# LPCXpresso55SXX_POWER-USB.net
KiCad netlist of a schematic drawn in Altium Designer
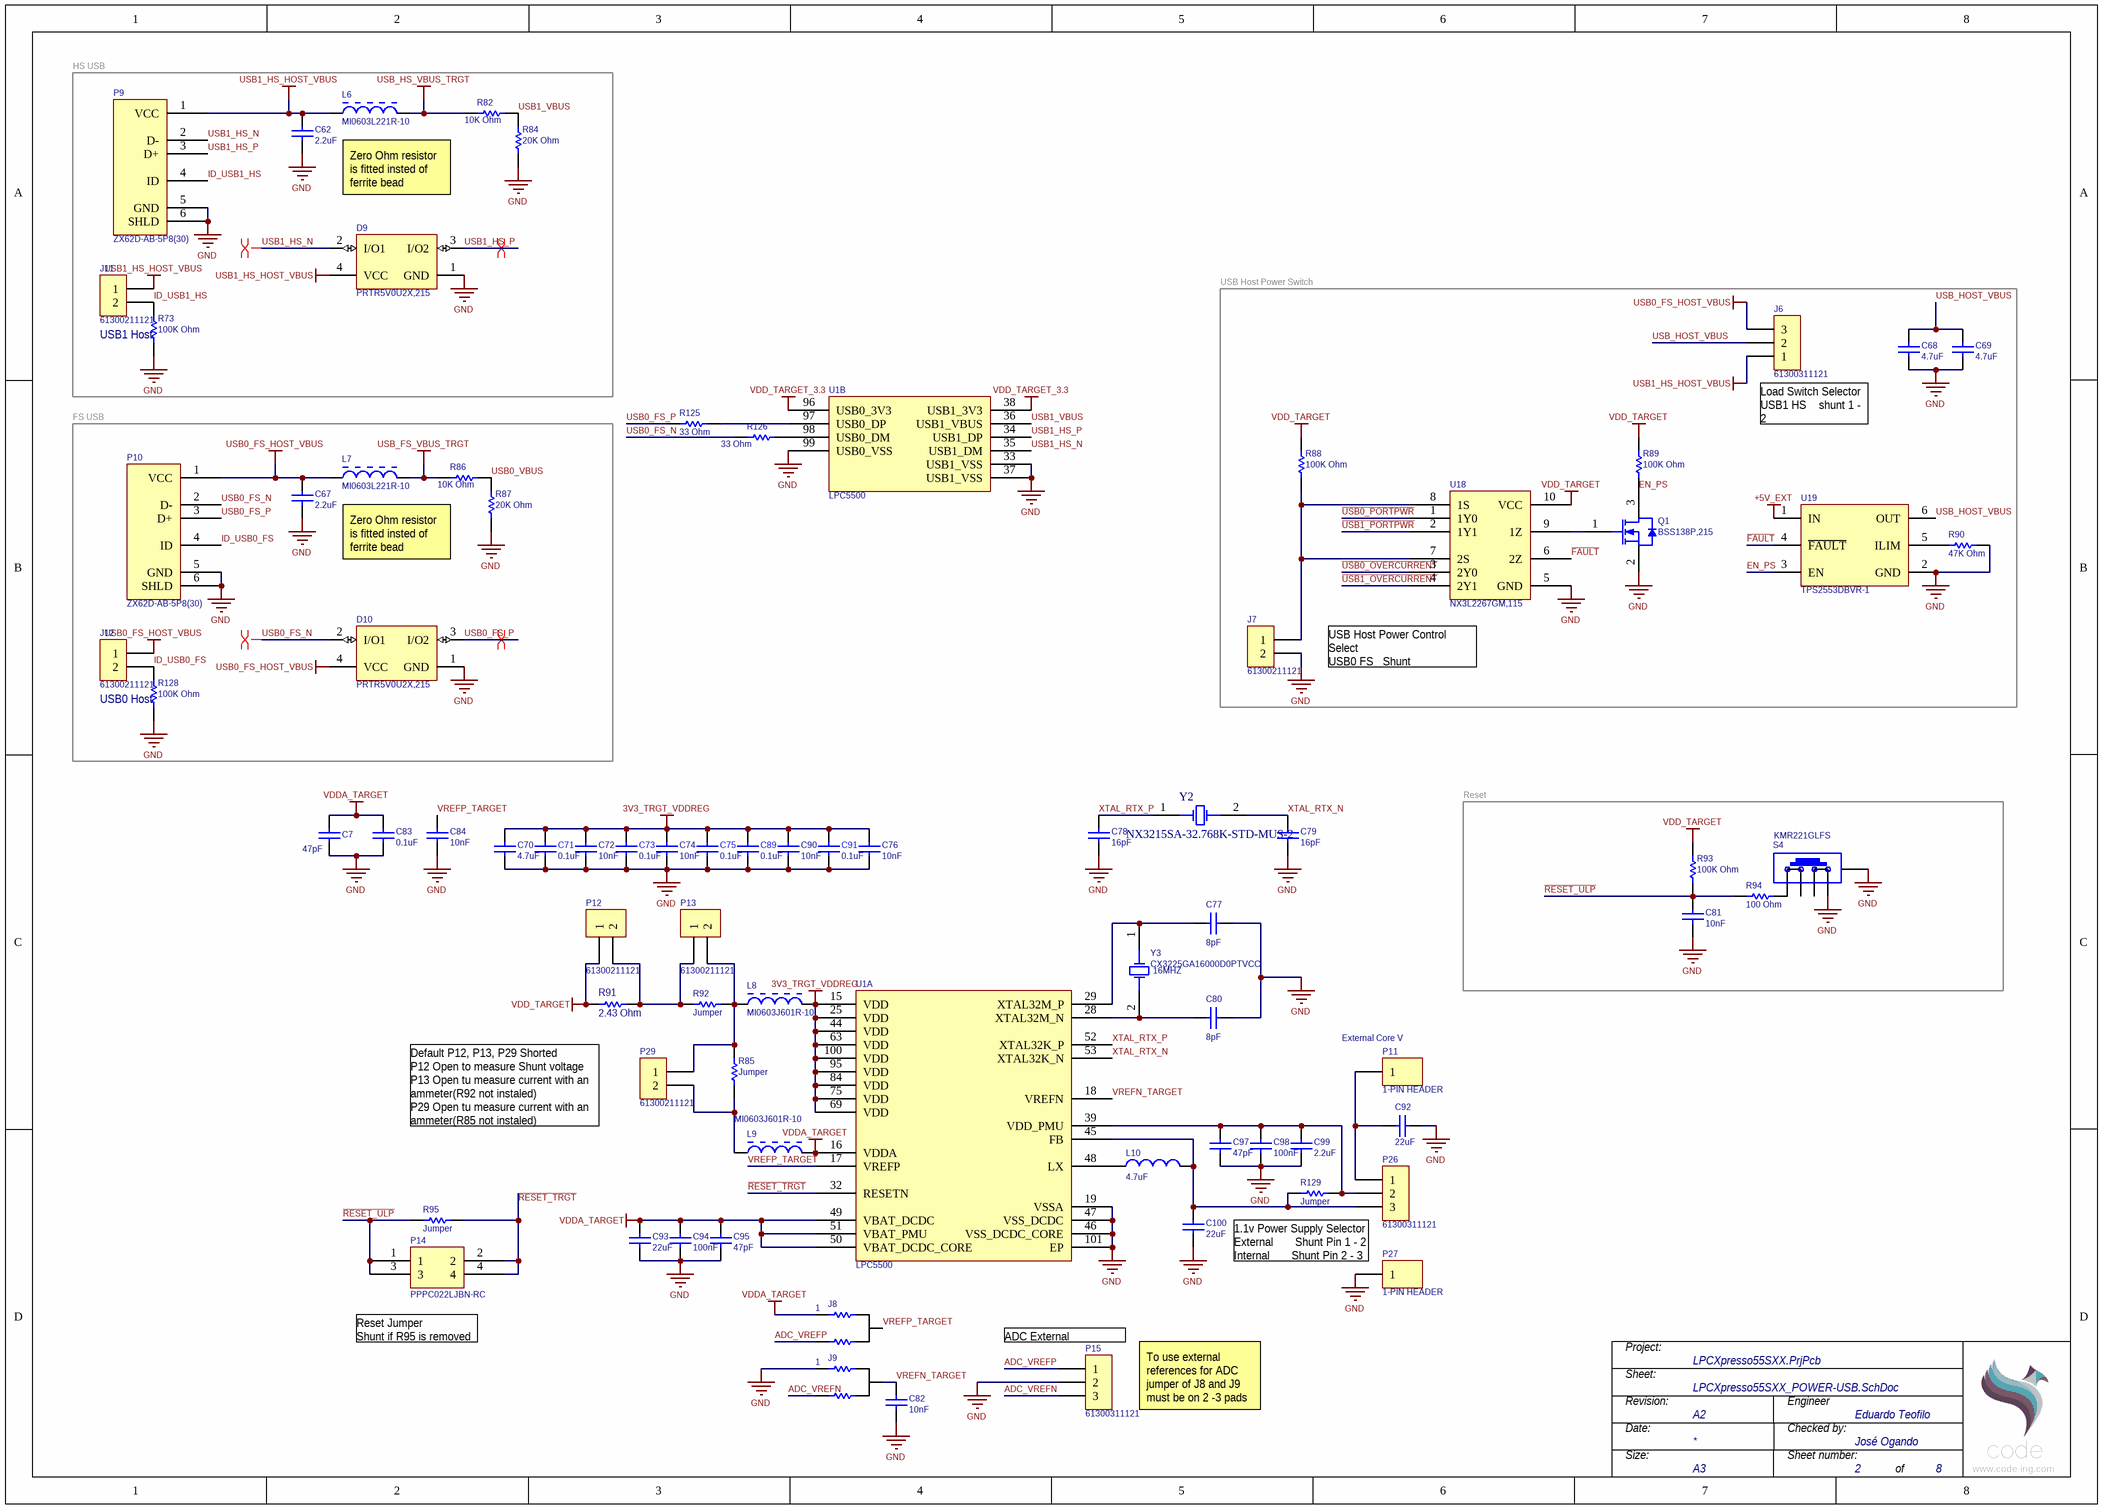
[diagram p0: LPCXpresso55SXX_POWER-USB.SchDoc]

(export (version "E")
  (design (tool "Eeschema 10.0.6"))
  (components
    (comp (ref "C7")
      (value "47pF")
      (footprint "CAPC0402(1005)60_L")
      (description "CAP 47pF 16V ±1% 0402 (1005 Metric) Thickness 0.6mm SMD")
      (fields (field (name "TOLERANCE") "Â±1%") (field (name "Comment") "CAP 47pF 16V 0402(1005)"))
      (libsource (lib "Altium Content Vault") (part "CMP-1034-01078-1"))
    )
    (comp (ref "C62")
      (value "2.2uF")
      (footprint "CAPC0402(1005)60_L")
      (description "CAP 2.2uF 10V ±10% 0402 (1005 Metric) Thickness 0.6mm SMD")
      (fields (field (name "TOLERANCE") "Â±10%") (field (name "Comment") "CAP 2.2uF 10V 0402(1005)"))
      (libsource (lib "Altium Content Vault") (part "CMP-1034-02127-1"))
    )
    (comp (ref "C67")
      (value "2.2uF")
      (footprint "CAPC0402(1005)60_L")
      (description "CAP 2.2uF 10V ±10% 0402 (1005 Metric) Thickness 0.6mm SMD")
      (fields (field (name "TOLERANCE") "Â±10%") (field (name "Comment") "CAP 2.2uF 10V 0402(1005)"))
      (libsource (lib "Altium Content Vault") (part "CMP-1034-02127-1"))
    )
    (comp (ref "C68")
      (value "4.7uF")
      (footprint "CAPC0603(1608)100_L")
      (description "CAP 4.7uF 10V ±10% 0603 (1608 Metric) Thickness 1mm SMD")
      (fields (field (name "TOLERANCE") "Â±10%") (field (name "Comment") "CAP 4.7uF 10V 0603(1608)"))
      (libsource (lib "Altium Content Vault") (part "CMP-1035-02785-1"))
    )
    (comp (ref "C69")
      (value "4.7uF")
      (footprint "CAPC0603(1608)100_L")
      (description "CAP 4.7uF 10V ±10% 0603 (1608 Metric) Thickness 1mm SMD")
      (fields (field (name "TOLERANCE") "Â±10%") (field (name "Comment") "CAP 4.7uF 10V 0603(1608)"))
      (libsource (lib "Altium Content Vault") (part "CMP-1035-02785-1"))
    )
    (comp (ref "C70")
      (value "4.7uF")
      (footprint "CAPC0603(1608)100_L")
      (description "CAP 4.7uF 10V ±10% 0603 (1608 Metric) Thickness 1mm SMD")
      (fields (field (name "TOLERANCE") "Â±10%") (field (name "Comment") "CAP 4.7uF 10V 0603(1608)"))
      (libsource (lib "Altium Content Vault") (part "CMP-1035-02785-1"))
    )
    (comp (ref "C71")
      (value "0.1uF")
      (footprint "CAPC1005")
      (description "Capacitor, Yageo, Ceramic, 0.1uF 10% 16V 0402 (1005) X7R")
      (fields
        (field (name "TOLERANCE") "10 %")
        (field (name "Comment") "CC0402KRX7R7BB104")
        (field (name "PUBLISHER") "Altium")
      )
      (libsource (lib "Altium Content Vault") (part "CMP-0001-00074-1"))
    )
    (comp (ref "C72")
      (value "10nF")
      (footprint "CAPC0402(1005)60_L")
      (description "CAP 10nF 25V ±10% 0402 (1005 Metric) Thickness 0.6mm SMD")
      (fields (field (name "TOLERANCE") "Â±10%") (field (name "Comment") "CAP 10nF 25V 0402(1005)"))
      (libsource (lib "Altium Content Vault") (part "CMP-1034-01880-1"))
    )
    (comp (ref "C73")
      (value "0.1uF")
      (footprint "CAPC1005")
      (description "Capacitor, Yageo, Ceramic, 0.1uF 10% 16V 0402 (1005) X7R")
      (fields
        (field (name "TOLERANCE") "10 %")
        (field (name "Comment") "CC0402KRX7R7BB104")
        (field (name "PUBLISHER") "Altium")
      )
      (libsource (lib "Altium Content Vault") (part "CMP-0001-00074-1"))
    )
    (comp (ref "C74")
      (value "10nF")
      (footprint "CAPC0402(1005)60_L")
      (description "CAP 10nF 25V ±10% 0402 (1005 Metric) Thickness 0.6mm SMD")
      (fields (field (name "TOLERANCE") "Â±10%") (field (name "Comment") "CAP 10nF 25V 0402(1005)"))
      (libsource (lib "Altium Content Vault") (part "CMP-1034-01880-1"))
    )
    (comp (ref "C75")
      (value "0.1uF")
      (footprint "CAPC1005")
      (description "Capacitor, Yageo, Ceramic, 0.1uF 10% 16V 0402 (1005) X7R")
      (fields
        (field (name "TOLERANCE") "10 %")
        (field (name "Comment") "CC0402KRX7R7BB104")
        (field (name "PUBLISHER") "Altium")
      )
      (libsource (lib "Altium Content Vault") (part "CMP-0001-00074-1"))
    )
    (comp (ref "C76")
      (value "10nF")
      (footprint "CAPC0402(1005)60_L")
      (description "CAP 10nF 25V ±10% 0402 (1005 Metric) Thickness 0.6mm SMD")
      (fields (field (name "TOLERANCE") "Â±10%") (field (name "Comment") "CAP 10nF 25V 0402(1005)"))
      (libsource (lib "Altium Content Vault") (part "CMP-1034-01880-1"))
    )
    (comp (ref "C77")
      (value "8pF")
      (footprint "0402_L")
      (description "CAP CER 8PF 25V C0G/NP0 0402")
      (fields
        (field (name "MANUFACTURER PART #") "GRM1555C1E8R0CA01D")
        (field (name "MANUFACTURER") "Murata Electronics North America")
        (field (name "MODIFIED BY") "*")
        (field (name "CREATED BY") "*")
      )
      (libsource (lib "CODE Miscellaneous Devices") (part "Capacitor"))
    )
    (comp (ref "C78")
      (value "16pF")
      (footprint "CAPC0402(1005)60_L")
      (description "CAP 16pF 25V ±0.5pF 0402 (1005 Metric) Thickness 0.6mm SMD")
      (fields (field (name "TOLERANCE") "Â±0.5pF") (field (name "Comment") "CAP 16pF 25V 0402(1005)"))
      (libsource (lib "Altium Content Vault") (part "CMP-1034-00833-1"))
    )
    (comp (ref "C79")
      (value "16pF")
      (footprint "CAPC0402(1005)60_L")
      (description "CAP 16pF 25V ±0.5pF 0402 (1005 Metric) Thickness 0.6mm SMD")
      (fields (field (name "TOLERANCE") "Â±0.5pF") (field (name "Comment") "CAP 16pF 25V 0402(1005)"))
      (libsource (lib "Altium Content Vault") (part "CMP-1034-00833-1"))
    )
    (comp (ref "C80")
      (value "8pF")
      (footprint "0402_L")
      (description "CAP CER 8PF 25V C0G/NP0 0402")
      (fields
        (field (name "MANUFACTURER PART #") "GRM1555C1E8R0CA01D")
        (field (name "MANUFACTURER") "Murata Electronics North America")
        (field (name "MODIFIED BY") "*")
        (field (name "CREATED BY") "*")
      )
      (libsource (lib "CODE Miscellaneous Devices") (part "Capacitor"))
    )
    (comp (ref "C81")
      (value "10nF")
      (footprint "CAPC0402(1005)60_L")
      (description "CAP 10nF 25V ±10% 0402 (1005 Metric) Thickness 0.6mm SMD")
      (fields (field (name "TOLERANCE") "Â±10%") (field (name "Comment") "CAP 10nF 25V 0402(1005)"))
      (libsource (lib "Altium Content Vault") (part "CMP-1034-01880-1"))
    )
    (comp (ref "C82")
      (value "10nF")
      (footprint "CAPC0402(1005)60_L")
      (description "CAP 10nF 25V ±10% 0402 (1005 Metric) Thickness 0.6mm SMD")
      (fields (field (name "TOLERANCE") "Â±10%") (field (name "Comment") "CAP 10nF 25V 0402(1005)"))
      (libsource (lib "Altium Content Vault") (part "CMP-1034-01880-1"))
    )
    (comp (ref "C83")
      (value "0.1uF")
      (footprint "CAPC1005")
      (description "Capacitor, Yageo, Ceramic, 0.1uF 10% 16V 0402 (1005) X7R")
      (fields
        (field (name "TOLERANCE") "10 %")
        (field (name "Comment") "CC0402KRX7R7BB104")
        (field (name "PUBLISHER") "Altium")
      )
      (libsource (lib "Altium Content Vault") (part "CMP-0001-00074-1"))
    )
    (comp (ref "C84")
      (value "10nF")
      (footprint "CAPC0402(1005)60_L")
      (description "CAP 10nF 25V ±10% 0402 (1005 Metric) Thickness 0.6mm SMD")
      (fields (field (name "TOLERANCE") "Â±10%") (field (name "Comment") "CAP 10nF 25V 0402(1005)"))
      (libsource (lib "Altium Content Vault") (part "CMP-1034-01880-1"))
    )
    (comp (ref "C89")
      (value "0.1uF")
      (footprint "CAPC1005")
      (description "Capacitor, Yageo, Ceramic, 0.1uF 10% 16V 0402 (1005) X7R")
      (fields
        (field (name "TOLERANCE") "10 %")
        (field (name "Comment") "CC0402KRX7R7BB104")
        (field (name "PUBLISHER") "Altium")
      )
      (libsource (lib "Altium Content Vault") (part "CMP-0001-00074-1"))
    )
    (comp (ref "C90")
      (value "10nF")
      (footprint "CAPC0402(1005)60_L")
      (description "CAP 10nF 25V ±10% 0402 (1005 Metric) Thickness 0.6mm SMD")
      (fields (field (name "TOLERANCE") "Â±10%") (field (name "Comment") "CAP 10nF 25V 0402(1005)"))
      (libsource (lib "Altium Content Vault") (part "CMP-1034-01880-1"))
    )
    (comp (ref "C91")
      (value "0.1uF")
      (footprint "CAPC1005")
      (description "Capacitor, Yageo, Ceramic, 0.1uF 10% 16V 0402 (1005) X7R")
      (fields
        (field (name "TOLERANCE") "10 %")
        (field (name "Comment") "CC0402KRX7R7BB104")
        (field (name "PUBLISHER") "Altium")
      )
      (libsource (lib "Altium Content Vault") (part "CMP-0001-00074-1"))
    )
    (comp (ref "C92")
      (value "22uF")
      (footprint "CAPC0805(2012)145_L")
      (description "CAP 22uF 16V ±20% 0805 (2012 Metric) Thickness 1.45mm SMD")
      (fields (field (name "TOLERANCE") "Â±20%") (field (name "Comment") "CAP 22uF 16V 0805(2012)"))
      (libsource (lib "Altium Content Vault") (part "CMP-1036-04946-1"))
    )
    (comp (ref "C93")
      (value "22uF")
      (footprint "CAPC0805(2012)145_L")
      (description "CAP 22uF 16V ±20% 0805 (2012 Metric) Thickness 1.45mm SMD")
      (fields (field (name "TOLERANCE") "Â±20%") (field (name "Comment") "CAP 22uF 16V 0805(2012)"))
      (libsource (lib "Altium Content Vault") (part "CMP-1036-04946-1"))
    )
    (comp (ref "C94")
      (value "100nF")
      (footprint "CAPC0603(1608)100_L")
      (description "CAP 100nF 25V ±20% 0603 (1608 Metric) Thickness 1mm SMD")
      (fields (field (name "TOLERANCE") "Â±20%") (field (name "Comment") "CAP 100nF 25V 0603(1608)"))
      (libsource (lib "Altium Content Vault") (part "CMP-1035-02589-1"))
    )
    (comp (ref "C95")
      (value "47pF")
      (footprint "CAPC0603(1608)100_L")
      (description "CAP 47pF 16V ±5pF 0603 (1608 Metric) Thickness 1mm SMD")
      (fields (field (name "TOLERANCE") "±5pF") (field (name "Comment") "CAP 47pF 16V 0603(1608)"))
      (libsource (lib "Altium Content Vault") (part "CMP-1035-01048-1"))
    )
    (comp (ref "C97")
      (value "47pF")
      (footprint "CAPC0603(1608)100_L")
      (description "CAP 47pF 16V ±5pF 0603 (1608 Metric) Thickness 1mm SMD")
      (fields (field (name "TOLERANCE") "±5pF") (field (name "Comment") "CAP 47pF 16V 0603(1608)"))
      (libsource (lib "Altium Content Vault") (part "CMP-1035-01048-1"))
    )
    (comp (ref "C98")
      (value "100nF")
      (footprint "CAPC0603(1608)100_L")
      (description "CAP 100nF 25V ±20% 0603 (1608 Metric) Thickness 1mm SMD")
      (fields (field (name "TOLERANCE") "Â±20%") (field (name "Comment") "CAP 100nF 25V 0603(1608)"))
      (libsource (lib "Altium Content Vault") (part "CMP-1035-02589-1"))
    )
    (comp (ref "C99")
      (value "2.2uF")
      (footprint "CAPC0402(1005)60_L")
      (description "CAP 2.2uF 10V ±10% 0402 (1005 Metric) Thickness 0.6mm SMD")
      (fields (field (name "TOLERANCE") "Â±10%") (field (name "Comment") "CAP 2.2uF 10V 0402(1005)"))
      (libsource (lib "Altium Content Vault") (part "CMP-1034-02127-1"))
    )
    (comp (ref "C100")
      (value "22uF")
      (footprint "CAPC0805(2012)145_L")
      (description "CAP 22uF 16V ±20% 0805 (2012 Metric) Thickness 1.45mm SMD")
      (fields (field (name "TOLERANCE") "Â±20%") (field (name "Comment") "CAP 22uF 16V 0805(2012)"))
      (libsource (lib "Altium Content Vault") (part "CMP-1036-04946-1"))
    )
    (comp (ref "D9")
      (value "PRTR5V0U2X,215")
      (footprint "NXP-SOT143B-4_V")
      (fields (field (name "MANUFACTURER") "NXP Semiconductors"))
      (libsource (lib "Altium Content Vault") (part "NXP-PRTR5V0U2X,215-4"))
    )
    (comp (ref "D10")
      (value "PRTR5V0U2X,215")
      (footprint "NXP-SOT143B-4_V")
      (fields (field (name "MANUFACTURER") "NXP Semiconductors"))
      (libsource (lib "Altium Content Vault") (part "NXP-PRTR5V0U2X,215-4"))
    )
    (comp (ref "J6")
      (value "61300311121")
      (footprint "61300311121")
      (description "HEADER 3POS SNGL T/H 2.54MM")
      (fields
        (field (name "MANUFACTURER") "Wurth Electronics Inc")
        (field (name "MODIFIED BY") "*")
        (field (name "CREATED BY") "gmoreno")
      )
      (libsource (lib "") (part "61300311121_1"))
    )
    (comp (ref "J7")
      (value "61300211121")
      (footprint "61300211121")
      (description "HEADER 2POS SNGL T/H 2.54MM")
      (fields
        (field (name "MANUFACTURER") "Wurth Electronics Inc")
        (field (name "MODIFIED BY") "*")
        (field (name "CREATED BY") "gmoreno")
      )
      (libsource (lib "Rectangular - Headers, Male Pins") (part "61300211121"))
    )
    (comp (ref "J8")
      (value "Resistor - Jumper")
      (footprint "0402_R - JMP")
      (fields (field (name "CREATED BY") "*") (field (name "MODIFIED BY") "*"))
      (libsource (lib "CODE Miscellaneous Devices") (part "Resistor - Jumper"))
    )
    (comp (ref "J9")
      (value "Resistor - Jumper")
      (footprint "0402_R - JMP")
      (fields (field (name "CREATED BY") "*") (field (name "MODIFIED BY") "*"))
      (libsource (lib "CODE Miscellaneous Devices") (part "Resistor - Jumper"))
    )
    (comp (ref "J11")
      (value "61300211121")
      (footprint "61300211121")
      (description "HEADER 2POS SNGL T/H 2.54MM")
      (fields
        (field (name "MANUFACTURER") "Wurth Electronics Inc")
        (field (name "MODIFIED BY") "*")
        (field (name "CREATED BY") "gmoreno")
      )
      (libsource (lib "Rectangular - Headers, Male Pins") (part "61300211121"))
    )
    (comp (ref "J12")
      (value "61300211121")
      (footprint "61300211121")
      (description "HEADER 2POS SNGL T/H 2.54MM")
      (fields
        (field (name "MANUFACTURER") "Wurth Electronics Inc")
        (field (name "MODIFIED BY") "*")
        (field (name "CREATED BY") "gmoreno")
      )
      (libsource (lib "Rectangular - Headers, Male Pins") (part "61300211121"))
    )
    (comp (ref "L6")
      (value "MI0603L221R-10")
      (footprint "LIRD-HZ0603C601R-10-2_V")
      (description "Chip Bead, 100 MHz, 2 A, -40 to 125 degC, 2-Pin SMD (0603), RoHS, Tape and Reel")
      (fields (field (name "MANUFACTURER") "LairdTechnologies"))
      (libsource (lib "Altium Content Vault") (part "IND-FB-2"))
    )
    (comp (ref "L7")
      (value "MI0603L221R-10")
      (footprint "LIRD-HZ0603C601R-10-2_V")
      (description "Chip Bead, 100 MHz, 2 A, -40 to 125 degC, 2-Pin SMD (0603), RoHS, Tape and Reel")
      (fields (field (name "MANUFACTURER") "LairdTechnologies"))
      (libsource (lib "Altium Content Vault") (part "IND-FB-2"))
    )
    (comp (ref "L8")
      (value "MI0603J601R-10")
      (footprint "LIRD-MI0603J601R-10_V")
      (description "Ferrite Bead, 600 Ohm, 1 A, -40 to 125 degC, 2-Pin SMD, RoHS, Tape and Reel")
      (fields (field (name "MANUFACTURER") "Laird"))
      (libsource (lib "Altium Content Vault") (part "IND-FB-2"))
    )
    (comp (ref "L9")
      (value "MI0603J601R-10")
      (footprint "LIRD-MI0603J601R-10_V")
      (description "Ferrite Bead, 600 Ohm, 1 A, -40 to 125 degC, 2-Pin SMD, RoHS, Tape and Reel")
      (fields (field (name "MANUFACTURER") "Laird"))
      (libsource (lib "Altium Content Vault") (part "IND-FB-2"))
    )
    (comp (ref "L10")
      (value "4.7uF")
      (footprint "0805(2012)")
      (description "FIXED IND 4.7UH 400MA 340 MOHM")
      (fields
        (field (name "MANUFACTURER PART #") "MLZ2012M4R7HT000")
        (field (name "MANUFACTURER") "TDK Corporation")
        (field (name "MODIFIED BY") "*")
        (field (name "CREATED BY") "eteofilo")
      )
      (libsource (lib "Fixed") (part "MLZ2012M4R7HT000"))
    )
    (comp (ref "P9")
      (value "ZX62D-AB-5P8(30)")
      (footprint "ZX62D-AB-5P8(30)")
      (description "CONN RCPT USB MICRO AB SMD")
      (fields
        (field (name "MANUFACTURER") "Hirose Electric Co Ltd")
        (field (name "CREATED BY") "eteofilo")
        (field (name "MODIFIED BY") "*")
      )
      (libsource (lib "USB, DVI, HDMI Connectors") (part "ZX62D-AB-5P8(30)"))
    )
    (comp (ref "P10")
      (value "ZX62D-AB-5P8(30)")
      (footprint "ZX62D-AB-5P8(30)")
      (description "CONN RCPT USB MICRO AB SMD")
      (fields
        (field (name "MANUFACTURER") "Hirose Electric Co Ltd")
        (field (name "CREATED BY") "eteofilo")
        (field (name "MODIFIED BY") "*")
      )
      (libsource (lib "USB, DVI, HDMI Connectors") (part "ZX62D-AB-5P8(30)"))
    )
    (comp (ref "P11")
      (value "1-PIN HEADER")
      (footprint "HDR1X1")
      (description "PTH HEADER 40MIL DRILL 70MIL PAD")
      (libsource (lib "CODE Miscellaneous Connectors") (part "1-PIN HEADER"))
    )
    (comp (ref "P12")
      (value "61300211121")
      (footprint "61300211121")
      (description "HEADER 2POS SNGL T/H 2.54MM")
      (fields
        (field (name "MANUFACTURER") "Wurth Electronics Inc")
        (field (name "MODIFIED BY") "*")
        (field (name "CREATED BY") "gmoreno")
      )
      (libsource (lib "") (part "61300211121_1"))
    )
    (comp (ref "P13")
      (value "61300211121")
      (footprint "61300211121")
      (description "HEADER 2POS SNGL T/H 2.54MM")
      (fields
        (field (name "MANUFACTURER") "Wurth Electronics Inc")
        (field (name "MODIFIED BY") "*")
        (field (name "CREATED BY") "gmoreno")
      )
      (libsource (lib "") (part "61300211121_1"))
    )
    (comp (ref "P14")
      (value "PPPC022LJBN-RC")
      (footprint "PPPC022LJBN-RC")
      (description "CONN FEMALE 4POS DL .1\" R/A GOLD")
      (fields
        (field (name "MANUFACTURER") "Sullins Connector Solutions")
        (field (name "CREATED BY") "eteofilo")
        (field (name "MODIFIED BY") "*")
      )
      (libsource (lib "Rectangular - Headers, Receptacles, Female Sockets") (part "PPPC022LJBN-RC"))
    )
    (comp (ref "P15")
      (value "61300311121")
      (footprint "61300311121")
      (description "HEADER 3POS SNGL T/H 2.54MM")
      (fields
        (field (name "MANUFACTURER") "Wurth Electronics Inc")
        (field (name "MODIFIED BY") "*")
        (field (name "CREATED BY") "gmoreno")
      )
      (libsource (lib "Rectangular - Headers, Male Pins") (part "61300311121"))
    )
    (comp (ref "P26")
      (value "61300311121")
      (footprint "61300311121")
      (description "HEADER 3POS SNGL T/H 2.54MM")
      (fields
        (field (name "MANUFACTURER") "Wurth Electronics Inc")
        (field (name "MODIFIED BY") "*")
        (field (name "CREATED BY") "gmoreno")
      )
      (libsource (lib "Rectangular - Headers, Male Pins") (part "61300311121"))
    )
    (comp (ref "P27")
      (value "1-PIN HEADER")
      (footprint "HDR1X1")
      (description "PTH HEADER 40MIL DRILL 70MIL PAD")
      (libsource (lib "CODE Miscellaneous Connectors") (part "1-PIN HEADER"))
    )
    (comp (ref "P29")
      (value "61300211121")
      (footprint "61300211121")
      (description "HEADER 2POS SNGL T/H 2.54MM")
      (fields
        (field (name "MANUFACTURER") "Wurth Electronics Inc")
        (field (name "MODIFIED BY") "*")
        (field (name "CREATED BY") "gmoreno")
      )
      (libsource (lib "Rectangular - Headers, Male Pins") (part "61300211121"))
    )
    (comp (ref "Q1")
      (value "BSS138P,215")
      (footprint "NXP-SOT23_N")
      (description "N-Channel Trench MOSFET, 60 V, 0.36 A, -55 to 150 degC, 3-Pin SOT23, Tape and Reel")
      (fields (field (name "MANUFACTURER") "NXP Semiconductors"))
      (libsource (lib "Altium Content Vault") (part "NXP-NMOS-GSD-3_B"))
    )
    (comp (ref "R73")
      (value "100K Ohm")
      (footprint "RESC1005X40X25LL05T05")
      (description "Chip Resistor, 100 KOhm, +/- 1%, 100 mW, -55 to 155 degC, 0402 (1005 Metric), RoHS, Tape and Reel")
      (fields (field (name "TOLERANCE") "1%") (field (name "MANUFACTURER") "Basic Passives"))
      (libsource (lib "Altium Content Vault") (part "CMP-2002-00608-3"))
    )
    (comp (ref "R82")
      (value "10K Ohm")
      (footprint "RESC0402(1005)_N")
      (description "10K 0.063W 1% 0402 (1005 Metric)  SMD")
      (fields (field (name "TOLERANCE") "1 %") (field (name "POWER") "0.063 W"))
      (libsource (lib "Altium Content Vault") (part "CMP-1011-00623-1"))
    )
    (comp (ref "R84")
      (value "20K Ohm")
      (footprint "RESC0402(1005)_M")
      (description "20K 0.063W 1% 0402 (1005 Metric)  SMD")
      (fields (field (name "POWER") "0.063 W") (field (name "TOLERANCE") "1 %"))
      (libsource (lib "Altium Content Vault") (part "CMP-1011-00655-1"))
    )
    (comp (ref "R85")
      (value "Jumper")
      (footprint "RESC0402(1005)_L")
      (description "Jumper 0402 (1005 Metric)")
      (fields (field (name "TOLERANCE") "None"))
      (libsource (lib "Altium Content Vault") (part "CMP-1011-00001-1"))
    )
    (comp (ref "R86")
      (value "10K Ohm")
      (footprint "RESC0402(1005)_N")
      (description "10K 0.063W 1% 0402 (1005 Metric)  SMD")
      (fields (field (name "TOLERANCE") "1 %") (field (name "POWER") "0.063 W"))
      (libsource (lib "Altium Content Vault") (part "CMP-1011-00623-1"))
    )
    (comp (ref "R87")
      (value "20K Ohm")
      (footprint "RESC0402(1005)_M")
      (description "20K 0.063W 1% 0402 (1005 Metric)  SMD")
      (fields (field (name "POWER") "0.063 W") (field (name "TOLERANCE") "1 %"))
      (libsource (lib "Altium Content Vault") (part "CMP-1011-00655-1"))
    )
    (comp (ref "R88")
      (value "100K Ohm")
      (footprint "RESC1005X40X25LL05T05")
      (description "Chip Resistor, 100 KOhm, +/- 1%, 100 mW, -55 to 155 degC, 0402 (1005 Metric), RoHS, Tape and Reel")
      (fields (field (name "TOLERANCE") "1%") (field (name "MANUFACTURER") "Basic Passives"))
      (libsource (lib "Altium Content Vault") (part "CMP-2002-00608-3"))
    )
    (comp (ref "R89")
      (value "100K Ohm")
      (footprint "RESC1005X40X25LL05T05")
      (description "Chip Resistor, 100 KOhm, +/- 1%, 100 mW, -55 to 155 degC, 0402 (1005 Metric), RoHS, Tape and Reel")
      (fields (field (name "TOLERANCE") "1%") (field (name "MANUFACTURER") "Basic Passives"))
      (libsource (lib "Altium Content Vault") (part "CMP-2002-00608-3"))
    )
    (comp (ref "R90")
      (value "47K Ohm")
      (footprint "RESC0402(1005)_L")
      (description "47K 0.063W 1% 0402 (1005 Metric)  SMD")
      (fields (field (name "POWER") "0.063 W") (field (name "TOLERANCE") "1 %"))
      (libsource (lib "Altium Content Vault") (part "CMP-1011-00699-1"))
    )
    (comp (ref "R91")
      (value "2.43 Ohm")
      (footprint "RESC0402(1005)_L")
      (description "2R43 0.063W 1% 0402 (1005 Metric)  SMD")
      (fields (field (name "POWER") "0.063 W") (field (name "TOLERANCE") "1 %"))
      (libsource (lib "Altium Content Vault") (part "CMP-1011-00213-1"))
    )
    (comp (ref "R92")
      (value "Jumper")
      (footprint "RESC0402(1005)_L")
      (description "Jumper 0402 (1005 Metric)")
      (fields (field (name "TOLERANCE") "None"))
      (libsource (lib "Altium Content Vault") (part "CMP-1011-00001-1"))
    )
    (comp (ref "R93")
      (value "100K Ohm")
      (footprint "RESC1005X40X25LL05T05")
      (description "Chip Resistor, 100 KOhm, +/- 1%, 100 mW, -55 to 155 degC, 0402 (1005 Metric), RoHS, Tape and Reel")
      (fields (field (name "TOLERANCE") "1%") (field (name "MANUFACTURER") "Basic Passives"))
      (libsource (lib "Altium Content Vault") (part "CMP-2002-00608-3"))
    )
    (comp (ref "R94")
      (value "100 Ohm")
      (footprint "RESC0402(1005)_L")
      (description "100R 0.063W 5% 0402 (1005 Metric)  SMD")
      (fields (field (name "POWER") "0.063 W") (field (name "TOLERANCE") "5 %"))
      (libsource (lib "Altium Content Vault") (part "CMP-1011-00050-1"))
    )
    (comp (ref "R95")
      (value "Jumper")
      (footprint "RESC0402(1005)_L")
      (description "Jumper 0402 (1005 Metric)")
      (fields (field (name "TOLERANCE") "None"))
      (libsource (lib "Altium Content Vault") (part "CMP-1011-00001-1"))
    )
    (comp (ref "R125")
      (value "33 Ohm")
      (footprint "RESC0402(1005)_L")
      (description "33R 0.063W 1% 0402 (1005 Metric)  SMD")
      (fields (field (name "TOLERANCE") "1 %") (field (name "POWER") "0.063 W"))
      (libsource (lib "Altium Content Vault") (part "CMP-1011-00341-1"))
    )
    (comp (ref "R126")
      (value "33 Ohm")
      (footprint "RESC0402(1005)_L")
      (description "33R 0.063W 1% 0402 (1005 Metric)  SMD")
      (fields (field (name "TOLERANCE") "1 %") (field (name "POWER") "0.063 W"))
      (libsource (lib "Altium Content Vault") (part "CMP-1011-00341-1"))
    )
    (comp (ref "R128")
      (value "100K Ohm")
      (footprint "RESC1005X40X25LL05T05")
      (description "Chip Resistor, 100 KOhm, +/- 1%, 100 mW, -55 to 155 degC, 0402 (1005 Metric), RoHS, Tape and Reel")
      (fields (field (name "TOLERANCE") "1%") (field (name "MANUFACTURER") "Basic Passives"))
      (libsource (lib "Altium Content Vault") (part "CMP-2002-00608-3"))
    )
    (comp (ref "R129")
      (value "Jumper")
      (footprint "RESC0402(1005)_L")
      (description "Jumper 0402 (1005 Metric)")
      (fields (field (name "TOLERANCE") "None"))
      (libsource (lib "Altium Content Vault") (part "CMP-1011-00001-1"))
    )
    (comp (ref "S4")
      (value "KMR221GLFS")
      (footprint "KMR221GLFS")
      (description "SWITCH TACTILE SPST-NO 0.05A 32V")
      (fields
        (field (name "MANUFACTURER") "C&K")
        (field (name "CREATED BY") "eteofilo")
        (field (name "MODIFIED BY") "*")
      )
      (libsource (lib "Tactile") (part "KMR221GLFS"))
    )
    (comp (ref "U1")
      (value "LPC5500")
      (footprint "LQFP EP 100")
      (description "32-bit ARM Cortex-M33, 312 KB SRAM, LPC55XX Series")
      (fields
        (field (name "MANUFACTURER") "NXP")
        (field (name "CREATED BY") "eteofilo")
        (field (name "MODIFIED BY") "*")
      )
      (libsource (lib "Embedded - Microcontrollers") (part "LPC5500"))
    )
    (comp (ref "U18")
      (value "NX3L2267GM,115")
      (footprint "XQFN10")
      (description "IC ANALOG SWITCH SPDT 10XQFN")
      (fields
        (field (name "MANUFACTURER") "NXP USA Inc.")
        (field (name "MODIFIED BY") "*")
        (field (name "CREATED BY") "eteofilo")
      )
      (libsource (lib "Interface - Analog Switches") (part "NX3L2267GM,115"))
    )
    (comp (ref "U19")
      (value "TPS2553DBVR-1")
      (footprint "DBV0006A_N")
      (fields (field (name "MANUFACTURER") "Texas Instruments"))
      (libsource (lib "Altium Content Vault") (part "CMP-0337-00282-2"))
    )
    (comp (ref "Y2")
      (value "NX3215SA-32.768K-STD-MUS-2")
      (footprint "2-SMD 3.2x1.5mm")
      (description "CRYSTAL 32.7680KHZ 12.5PF SMD")
      (fields
        (field (name "MANUFACTURER") "NDK")
        (field (name "CREATED BY") "eteofilo")
        (field (name "MODIFIED BY") "*")
      )
      (libsource (lib "Crystals") (part "NX3215SA-32.768K-STD-MUS-2"))
    )
    (comp (ref "Y3")
      (value "CX3225GA16000D0PTVCC")
      (footprint "CX3225GA")
      (description "CRYSTAL 16.0000MHZ 8PF SMD")
      (fields
        (field (name "MANUFACTURER") "Kyocera International Inc. Electronic Components")
        (field (name "ALTIUM_VALUE") "16MHZ")
        (field (name "MODIFIED BY") "*")
        (field (name "CREATED BY") "eteofilo")
      )
      (libsource (lib "Crystals") (part "CX3225GA16000D0PTVCC"))
    )
  )
  (nets
    (net (code "1") (name "+5V_EXT") (class "Default")
      (node (ref "U19") (pin "1") (pinfunction "IN_1") (pintype "power_in"))
    )
    (net (code "2") (name "/ADC_VREFN") (class "Default")
      (node (ref "J9") (pin "3") (pinfunction "3_3") (pintype "passive"))
      (node (ref "P15") (pin "3") (pinfunction "3_3") (pintype "passive"))
    )
    (net (code "3") (name "/ADC_VREFP") (class "Default")
      (node (ref "J8") (pin "3") (pinfunction "3_3") (pintype "passive"))
      (node (ref "P15") (pin "1") (pinfunction "1_1") (pintype "passive"))
    )
    (net (code "4") (name "/EN_PS") (class "Default")
      (node (ref "Q1") (pin "3") (pinfunction "D_3") (pintype "passive"))
      (node (ref "R89") (pin "1") (pinfunction "1_1") (pintype "passive"))
      (node (ref "U19") (pin "3") (pinfunction "EN_3") (pintype "passive"))
    )
    (net (code "5") (name "/ID_USB0_FS") (class "Default")
      (node (ref "J12") (pin "2") (pinfunction "2_2") (pintype "passive"))
      (node (ref "P10") (pin "4") (pinfunction "ID_4") (pintype "passive"))
      (node (ref "R128") (pin "2") (pinfunction "2_2") (pintype "passive"))
    )
    (net (code "6") (name "/ID_USB1_HS") (class "Default")
      (node (ref "J11") (pin "2") (pinfunction "2_2") (pintype "passive"))
      (node (ref "P9") (pin "4") (pinfunction "ID_4") (pintype "passive"))
      (node (ref "R73") (pin "2") (pinfunction "2_2") (pintype "passive"))
    )
    (net (code "7") (name "/USB0_FS_N") (class "Default")
      (node (ref "D10") (pin "2") (pinfunction "I/O1_2") (pintype "bidirectional"))
      (node (ref "P10") (pin "2") (pinfunction "D-_2") (pintype "passive"))
      (node (ref "R126") (pin "1") (pinfunction "1_1") (pintype "passive"))
    )
    (net (code "8") (name "/USB0_FS_P") (class "Default")
      (node (ref "D10") (pin "3") (pinfunction "I/O2_3") (pintype "bidirectional"))
      (node (ref "P10") (pin "3") (pinfunction "D+_3") (pintype "passive"))
      (node (ref "R125") (pin "1") (pinfunction "1_1") (pintype "passive"))
    )
    (net (code "9") (name "/USB0_VBUS") (class "Default")
      (node (ref "R86") (pin "2") (pinfunction "2_2") (pintype "passive"))
      (node (ref "R87") (pin "2") (pinfunction "2_2") (pintype "passive"))
    )
    (net (code "10") (name "/USB1_HS_N") (class "Default")
      (node (ref "D9") (pin "2") (pinfunction "I/O1_2") (pintype "bidirectional"))
      (node (ref "P9") (pin "2") (pinfunction "D-_2") (pintype "passive"))
      (node (ref "U1") (pin "35") (pinfunction "USB1_DM_35") (pintype "passive"))
    )
    (net (code "11") (name "/USB1_HS_P") (class "Default")
      (node (ref "D9") (pin "3") (pinfunction "I/O2_3") (pintype "bidirectional"))
      (node (ref "P9") (pin "3") (pinfunction "D+_3") (pintype "passive"))
      (node (ref "U1") (pin "34") (pinfunction "USB1_DP_34") (pintype "passive"))
    )
    (net (code "12") (name "/USB1_VBUS") (class "Default")
      (node (ref "R82") (pin "2") (pinfunction "2_2") (pintype "passive"))
      (node (ref "R84") (pin "2") (pinfunction "2_2") (pintype "passive"))
      (node (ref "U1") (pin "36") (pinfunction "USB1_VBUS_36") (pintype "passive"))
    )
    (net (code "13") (name "/USB_HOST_VBUS") (class "Default")
      (node (ref "C68") (pin "2") (pinfunction "2_2") (pintype "passive"))
      (node (ref "C69") (pin "2") (pinfunction "2_2") (pintype "passive"))
      (node (ref "J6") (pin "2") (pinfunction "2_2") (pintype "passive"))
      (node (ref "U19") (pin "6") (pinfunction "OUT_6") (pintype "power_in"))
    )
    (net (code "14") (name "/VREFN_TARGET") (class "Default")
      (node (ref "C82") (pin "2") (pinfunction "2_2") (pintype "passive"))
      (node (ref "J9") (pin "2") (pinfunction "2_2") (pintype "passive"))
      (node (ref "U1") (pin "18") (pinfunction "VREFN_18") (pintype "passive"))
    )
    (net (code "15") (name "/VREFP_TARGET") (class "Default")
      (node (ref "C84") (pin "2") (pinfunction "2_2") (pintype "passive"))
      (node (ref "J8") (pin "2") (pinfunction "2_2") (pintype "passive"))
      (node (ref "U1") (pin "17") (pinfunction "VREFP_17") (pintype "passive"))
    )
    (net (code "16") (name "/XTAL_RTX_N") (class "Default")
      (node (ref "C79") (pin "2") (pinfunction "2_2") (pintype "passive"))
      (node (ref "U1") (pin "53") (pinfunction "XTAL32K_N_53") (pintype "passive"))
      (node (ref "Y2") (pin "2") (pinfunction "OSC2_2") (pintype "passive"))
    )
    (net (code "17") (name "/XTAL_RTX_P") (class "Default")
      (node (ref "C78") (pin "2") (pinfunction "2_2") (pintype "passive"))
      (node (ref "U1") (pin "52") (pinfunction "XTAL32K_P_52") (pintype "passive"))
      (node (ref "Y2") (pin "1") (pinfunction "OSC1_1") (pintype "passive"))
    )
    (net (code "18") (name "/~{FAULT}") (class "Default")
      (node (ref "U18") (pin "6") (pinfunction "2Z_6") (pintype "passive"))
      (node (ref "U19") (pin "4") (pinfunction "~{FAULT}_4") (pintype "tri_state"))
    )
    (net (code "19") (name "/~{RESET_TRGT}") (class "Default")
      (node (ref "P14") (pin "2") (pinfunction "2_2") (pintype "passive"))
      (node (ref "P14") (pin "4") (pinfunction "4_4") (pintype "passive"))
      (node (ref "R95") (pin "1") (pinfunction "1_1") (pintype "passive"))
      (node (ref "U1") (pin "32") (pinfunction "RESETN_32") (pintype "passive"))
    )
    (net (code "20") (name "/~{RESET_ULP}") (class "Default")
      (node (ref "C81") (pin "2") (pinfunction "2_2") (pintype "passive"))
      (node (ref "P14") (pin "1") (pinfunction "1_1") (pintype "passive"))
      (node (ref "P14") (pin "3") (pinfunction "3_3") (pintype "passive"))
      (node (ref "R93") (pin "1") (pinfunction "1_1") (pintype "passive"))
      (node (ref "R94") (pin "1") (pinfunction "1_1") (pintype "passive"))
      (node (ref "R95") (pin "2") (pinfunction "2_2") (pintype "passive"))
    )
    (net (code "21") (name "/~{USB0_OVERCURRENT}") (class "Default")
      (node (ref "U18") (pin "3") (pinfunction "2Y0_3") (pintype "passive"))
    )
    (net (code "22") (name "/~{USB0_PORTPWR}") (class "Default")
      (node (ref "U18") (pin "1") (pinfunction "1Y0_1") (pintype "passive"))
    )
    (net (code "23") (name "/~{USB1_OVERCURRENT}") (class "Default")
      (node (ref "U18") (pin "4") (pinfunction "2Y1_4") (pintype "passive"))
    )
    (net (code "24") (name "/~{USB1_PORTPWR}") (class "Default")
      (node (ref "U18") (pin "2") (pinfunction "1Y1_2") (pintype "passive"))
    )
    (net (code "25") (name "3V3_TRGT_VDDREG") (class "Default")
      (node (ref "C70") (pin "2") (pinfunction "2_2") (pintype "passive"))
      (node (ref "C71") (pin "1") (pinfunction "1_1") (pintype "passive"))
      (node (ref "C72") (pin "2") (pinfunction "2_2") (pintype "passive"))
      (node (ref "C73") (pin "1") (pinfunction "1_1") (pintype "passive"))
      (node (ref "C74") (pin "2") (pinfunction "2_2") (pintype "passive"))
      (node (ref "C75") (pin "1") (pinfunction "1_1") (pintype "passive"))
      (node (ref "C76") (pin "2") (pinfunction "2_2") (pintype "passive"))
      (node (ref "C89") (pin "1") (pinfunction "1_1") (pintype "passive"))
      (node (ref "C90") (pin "2") (pinfunction "2_2") (pintype "passive"))
      (node (ref "C91") (pin "1") (pinfunction "1_1") (pintype "passive"))
      (node (ref "L8") (pin "2") (pinfunction "2_2") (pintype "passive"))
      (node (ref "U1") (pin "100") (pinfunction "VDD_100") (pintype "passive"))
      (node (ref "U1") (pin "15") (pinfunction "VDD_15") (pintype "passive"))
      (node (ref "U1") (pin "25") (pinfunction "VDD_25") (pintype "passive"))
      (node (ref "U1") (pin "44") (pinfunction "VDD_44") (pintype "passive"))
      (node (ref "U1") (pin "63") (pinfunction "VDD_63") (pintype "passive"))
      (node (ref "U1") (pin "69") (pinfunction "VDD_69") (pintype "passive"))
      (node (ref "U1") (pin "75") (pinfunction "VDD_75") (pintype "passive"))
      (node (ref "U1") (pin "84") (pinfunction "VDD_84") (pintype "passive"))
      (node (ref "U1") (pin "95") (pinfunction "VDD_95") (pintype "passive"))
    )
    (net (code "26") (name "GND") (class "Default")
      (node (ref "C100") (pin "2") (pinfunction "2_2") (pintype "passive"))
      (node (ref "C62") (pin "1") (pinfunction "1_1") (pintype "passive"))
      (node (ref "C67") (pin "1") (pinfunction "1_1") (pintype "passive"))
      (node (ref "C68") (pin "1") (pinfunction "1_1") (pintype "passive"))
      (node (ref "C69") (pin "1") (pinfunction "1_1") (pintype "passive"))
      (node (ref "C7") (pin "1") (pinfunction "1_1") (pintype "passive"))
      (node (ref "C70") (pin "1") (pinfunction "1_1") (pintype "passive"))
      (node (ref "C71") (pin "2") (pinfunction "2_2") (pintype "passive"))
      (node (ref "C72") (pin "1") (pinfunction "1_1") (pintype "passive"))
      (node (ref "C73") (pin "2") (pinfunction "2_2") (pintype "passive"))
      (node (ref "C74") (pin "1") (pinfunction "1_1") (pintype "passive"))
      (node (ref "C75") (pin "2") (pinfunction "2_2") (pintype "passive"))
      (node (ref "C76") (pin "1") (pinfunction "1_1") (pintype "passive"))
      (node (ref "C77") (pin "2") (pinfunction "2_2") (pintype "passive"))
      (node (ref "C78") (pin "1") (pinfunction "1_1") (pintype "passive"))
      (node (ref "C79") (pin "1") (pinfunction "1_1") (pintype "passive"))
      (node (ref "C80") (pin "2") (pinfunction "2_2") (pintype "passive"))
      (node (ref "C81") (pin "1") (pinfunction "1_1") (pintype "passive"))
      (node (ref "C82") (pin "1") (pinfunction "1_1") (pintype "passive"))
      (node (ref "C83") (pin "2") (pinfunction "2_2") (pintype "passive"))
      (node (ref "C84") (pin "1") (pinfunction "1_1") (pintype "passive"))
      (node (ref "C89") (pin "2") (pinfunction "2_2") (pintype "passive"))
      (node (ref "C90") (pin "1") (pinfunction "1_1") (pintype "passive"))
      (node (ref "C91") (pin "2") (pinfunction "2_2") (pintype "passive"))
      (node (ref "C92") (pin "2") (pinfunction "2_2") (pintype "passive"))
      (node (ref "C93") (pin "1") (pinfunction "1_1") (pintype "passive"))
      (node (ref "C94") (pin "1") (pinfunction "1_1") (pintype "passive"))
      (node (ref "C95") (pin "1") (pinfunction "1_1") (pintype "passive"))
      (node (ref "C97") (pin "1") (pinfunction "1_1") (pintype "passive"))
      (node (ref "C98") (pin "1") (pinfunction "1_1") (pintype "passive"))
      (node (ref "C99") (pin "1") (pinfunction "1_1") (pintype "passive"))
      (node (ref "D10") (pin "1") (pinfunction "GND_1") (pintype "power_in"))
      (node (ref "D9") (pin "1") (pinfunction "GND_1") (pintype "power_in"))
      (node (ref "J7") (pin "2") (pinfunction "2_2") (pintype "passive"))
      (node (ref "J9") (pin "1") (pinfunction "1_1") (pintype "passive"))
      (node (ref "P10") (pin "5") (pinfunction "GND_5") (pintype "passive"))
      (node (ref "P10") (pin "6") (pinfunction "SHLD_6") (pintype "passive"))
      (node (ref "P15") (pin "2") (pinfunction "2_2") (pintype "passive"))
      (node (ref "P27") (pin "1") (pinfunction "1_1") (pintype "passive"))
      (node (ref "P9") (pin "5") (pinfunction "GND_5") (pintype "passive"))
      (node (ref "P9") (pin "6") (pinfunction "SHLD_6") (pintype "passive"))
      (node (ref "Q1") (pin "2") (pinfunction "S_2") (pintype "passive"))
      (node (ref "R128") (pin "1") (pinfunction "1_1") (pintype "passive"))
      (node (ref "R73") (pin "1") (pinfunction "1_1") (pintype "passive"))
      (node (ref "R84") (pin "1") (pinfunction "1_1") (pintype "passive"))
      (node (ref "R87") (pin "1") (pinfunction "1_1") (pintype "passive"))
      (node (ref "R90") (pin "2") (pinfunction "2_2") (pintype "passive"))
      (node (ref "S4") (pin "2") (pinfunction "2_2") (pintype "passive"))
      (node (ref "S4") (pin "5") (pinfunction "5_5") (pintype "passive"))
      (node (ref "U1") (pin "101") (pinfunction "EP_101") (pintype "passive"))
      (node (ref "U1") (pin "19") (pinfunction "VSSA_19") (pintype "passive"))
      (node (ref "U1") (pin "33") (pinfunction "USB1_VSS_33") (pintype "passive"))
      (node (ref "U1") (pin "37") (pinfunction "USB1_VSS_37") (pintype "passive"))
      (node (ref "U1") (pin "46") (pinfunction "VSS_DCDC_CORE_46") (pintype "passive"))
      (node (ref "U1") (pin "47") (pinfunction "VSS_DCDC_47") (pintype "passive"))
      (node (ref "U1") (pin "99") (pinfunction "USB0_VSS_99") (pintype "passive"))
      (node (ref "U18") (pin "5") (pinfunction "GND_5") (pintype "passive"))
      (node (ref "U19") (pin "2") (pinfunction "GND_2") (pintype "power_in"))
    )
    (net (code "27") (name "Net-(C92-Pad1)") (class "Default")
      (node (ref "C92") (pin "1") (pinfunction "1_1") (pintype "passive"))
      (node (ref "P11") (pin "1") (pinfunction "1_1") (pintype "passive"))
      (node (ref "P26") (pin "1") (pinfunction "1_1") (pintype "passive"))
    )
    (net (code "28") (name "Net-(L8-Pad1)") (class "Default")
      (node (ref "L8") (pin "1") (pinfunction "1_1") (pintype "passive"))
      (node (ref "P13") (pin "2") (pinfunction "2_2") (pintype "passive"))
      (node (ref "P29") (pin "1") (pinfunction "1_1") (pintype "passive"))
      (node (ref "R85") (pin "1") (pinfunction "1_1") (pintype "passive"))
      (node (ref "R92") (pin "1") (pinfunction "1_1") (pintype "passive"))
    )
    (net (code "29") (name "Net-(L9-Pad1)") (class "Default")
      (node (ref "L9") (pin "1") (pinfunction "1_1") (pintype "passive"))
      (node (ref "P29") (pin "2") (pinfunction "2_2") (pintype "passive"))
      (node (ref "R85") (pin "2") (pinfunction "2_2") (pintype "passive"))
    )
    (net (code "30") (name "Net-(P12-Pad2)") (class "Default")
      (node (ref "P12") (pin "2") (pinfunction "2_2") (pintype "passive"))
      (node (ref "P13") (pin "1") (pinfunction "1_1") (pintype "passive"))
      (node (ref "R91") (pin "2") (pinfunction "2_2") (pintype "passive"))
      (node (ref "R92") (pin "2") (pinfunction "2_2") (pintype "passive"))
    )
    (net (code "31") (name "Net-(Q1-G)") (class "Default")
      (node (ref "Q1") (pin "1") (pinfunction "G_1") (pintype "passive"))
      (node (ref "U18") (pin "9") (pinfunction "1Z_9") (pintype "passive"))
    )
    (net (code "32") (name "Net-(R94-Pad2)") (class "Default")
      (node (ref "R94") (pin "2") (pinfunction "2_2") (pintype "passive"))
      (node (ref "S4") (pin "1") (pinfunction "1_1") (pintype "passive"))
    )
    (net (code "33") (name "Net-(U1A-FB)") (class "Default")
      (node (ref "C100") (pin "1") (pinfunction "1_1") (pintype "passive"))
      (node (ref "L10") (pin "2") (pinfunction "2_2") (pintype "passive"))
      (node (ref "P26") (pin "3") (pinfunction "3_3") (pintype "passive"))
      (node (ref "R129") (pin "2") (pinfunction "2_2") (pintype "passive"))
      (node (ref "U1") (pin "45") (pinfunction "FB_45") (pintype "passive"))
    )
    (net (code "34") (name "Net-(U1A-LX)") (class "Default")
      (node (ref "L10") (pin "1") (pinfunction "1_1") (pintype "passive"))
      (node (ref "U1") (pin "48") (pinfunction "LX_48") (pintype "passive"))
    )
    (net (code "35") (name "Net-(U1A-VDD_PMU)") (class "Default")
      (node (ref "C97") (pin "2") (pinfunction "2_2") (pintype "passive"))
      (node (ref "C98") (pin "2") (pinfunction "2_2") (pintype "passive"))
      (node (ref "C99") (pin "2") (pinfunction "2_2") (pintype "passive"))
      (node (ref "P26") (pin "2") (pinfunction "2_2") (pintype "passive"))
      (node (ref "R129") (pin "1") (pinfunction "1_1") (pintype "passive"))
      (node (ref "U1") (pin "39") (pinfunction "VDD_PMU_39") (pintype "passive"))
    )
    (net (code "36") (name "Net-(U1A-XTAL32M_N)") (class "Default")
      (node (ref "C80") (pin "1") (pinfunction "1_1") (pintype "passive"))
      (node (ref "U1") (pin "28") (pinfunction "XTAL32M_N_28") (pintype "passive"))
      (node (ref "Y3") (pin "2") (pintype "passive"))
    )
    (net (code "37") (name "Net-(U1A-XTAL32M_P)") (class "Default")
      (node (ref "C77") (pin "1") (pinfunction "1_1") (pintype "passive"))
      (node (ref "U1") (pin "29") (pinfunction "XTAL32M_P_29") (pintype "passive"))
      (node (ref "Y3") (pin "1") (pinfunction "OSC1_1") (pintype "passive"))
    )
    (net (code "38") (name "Net-(U1B-USB0_DM)") (class "Default")
      (node (ref "R126") (pin "2") (pinfunction "2_2") (pintype "passive"))
      (node (ref "U1") (pin "98") (pinfunction "USB0_DM_98") (pintype "passive"))
    )
    (net (code "39") (name "Net-(U1B-USB0_DP)") (class "Default")
      (node (ref "R125") (pin "2") (pinfunction "2_2") (pintype "passive"))
      (node (ref "U1") (pin "97") (pinfunction "USB0_DP_97") (pintype "passive"))
    )
    (net (code "40") (name "Net-(U18-1S)") (class "Default")
      (node (ref "J7") (pin "1") (pinfunction "1_1") (pintype "passive"))
      (node (ref "R88") (pin "1") (pinfunction "1_1") (pintype "passive"))
      (node (ref "U18") (pin "7") (pinfunction "2S_7") (pintype "passive"))
      (node (ref "U18") (pin "8") (pinfunction "1S_8") (pintype "passive"))
    )
    (net (code "41") (name "Net-(U19-ILIM)") (class "Default")
      (node (ref "R90") (pin "1") (pinfunction "1_1") (pintype "passive"))
      (node (ref "U19") (pin "5") (pinfunction "ILIM_5") (pintype "passive"))
    )
    (net (code "42") (name "USB0_FS_HOST_VBUS") (class "Default")
      (node (ref "C67") (pin "2") (pinfunction "2_2") (pintype "passive"))
      (node (ref "D10") (pin "4") (pinfunction "VCC_4") (pintype "power_in"))
      (node (ref "J12") (pin "1") (pinfunction "1_1") (pintype "passive"))
      (node (ref "J6") (pin "3") (pinfunction "3_3") (pintype "passive"))
      (node (ref "L7") (pin "1") (pinfunction "1_1") (pintype "passive"))
      (node (ref "P10") (pin "1") (pinfunction "VCC_1") (pintype "passive"))
    )
    (net (code "43") (name "USB1_HS_HOST_VBUS") (class "Default")
      (node (ref "C62") (pin "2") (pinfunction "2_2") (pintype "passive"))
      (node (ref "D9") (pin "4") (pinfunction "VCC_4") (pintype "power_in"))
      (node (ref "J11") (pin "1") (pinfunction "1_1") (pintype "passive"))
      (node (ref "J6") (pin "1") (pinfunction "1_1") (pintype "passive"))
      (node (ref "L6") (pin "1") (pinfunction "1_1") (pintype "passive"))
      (node (ref "P9") (pin "1") (pinfunction "VCC_1") (pintype "passive"))
    )
    (net (code "44") (name "USB_FS_VBUS_TRGT") (class "Default")
      (node (ref "L7") (pin "2") (pinfunction "2_2") (pintype "passive"))
      (node (ref "R86") (pin "1") (pinfunction "1_1") (pintype "passive"))
    )
    (net (code "45") (name "USB_HS_VBUS_TRGT") (class "Default")
      (node (ref "L6") (pin "2") (pinfunction "2_2") (pintype "passive"))
      (node (ref "R82") (pin "1") (pinfunction "1_1") (pintype "passive"))
    )
    (net (code "46") (name "VDDA_TARGET") (class "Default")
      (node (ref "C7") (pin "2") (pinfunction "2_2") (pintype "passive"))
      (node (ref "C83") (pin "1") (pinfunction "1_1") (pintype "passive"))
      (node (ref "C93") (pin "2") (pinfunction "2_2") (pintype "passive"))
      (node (ref "C94") (pin "2") (pinfunction "2_2") (pintype "passive"))
      (node (ref "C95") (pin "2") (pinfunction "2_2") (pintype "passive"))
      (node (ref "J8") (pin "1") (pinfunction "1_1") (pintype "passive"))
      (node (ref "L9") (pin "2") (pinfunction "2_2") (pintype "passive"))
      (node (ref "U1") (pin "16") (pinfunction "VDDA_16") (pintype "passive"))
      (node (ref "U1") (pin "49") (pinfunction "VBAT_DCDC_49") (pintype "passive"))
      (node (ref "U1") (pin "50") (pinfunction "VBAT_DCDC_CORE_50") (pintype "passive"))
      (node (ref "U1") (pin "51") (pinfunction "VBAT_PMU_51") (pintype "passive"))
    )
    (net (code "47") (name "VDD_TARGET") (class "Default")
      (node (ref "P12") (pin "1") (pinfunction "1_1") (pintype "passive"))
      (node (ref "R88") (pin "2") (pinfunction "2_2") (pintype "passive"))
      (node (ref "R89") (pin "2") (pinfunction "2_2") (pintype "passive"))
      (node (ref "R91") (pin "1") (pinfunction "1_1") (pintype "passive"))
      (node (ref "R93") (pin "2") (pinfunction "2_2") (pintype "passive"))
      (node (ref "U18") (pin "10") (pinfunction "VCC_10") (pintype "passive"))
    )
    (net (code "48") (name "VDD_TARGET_3.3") (class "Default")
      (node (ref "U1") (pin "38") (pinfunction "USB1_3V3_38") (pintype "passive"))
      (node (ref "U1") (pin "96") (pinfunction "USB0_3V3_96") (pintype "passive"))
    )
    (net (code "49") (name "unconnected-(S4-Pad3)") (class "Default")
      (node (ref "S4") (pin "3") (pinfunction "3_3") (pintype "passive"))
    )
    (net (code "50") (name "unconnected-(S4-Pad4)") (class "Default")
      (node (ref "S4") (pin "4") (pinfunction "4_4") (pintype "passive"))
    )
  )
)
